# OBKP_Effector_PCB_MIKE_DID_IT.net
KiCad netlist of a schematic drawn in EAGLE
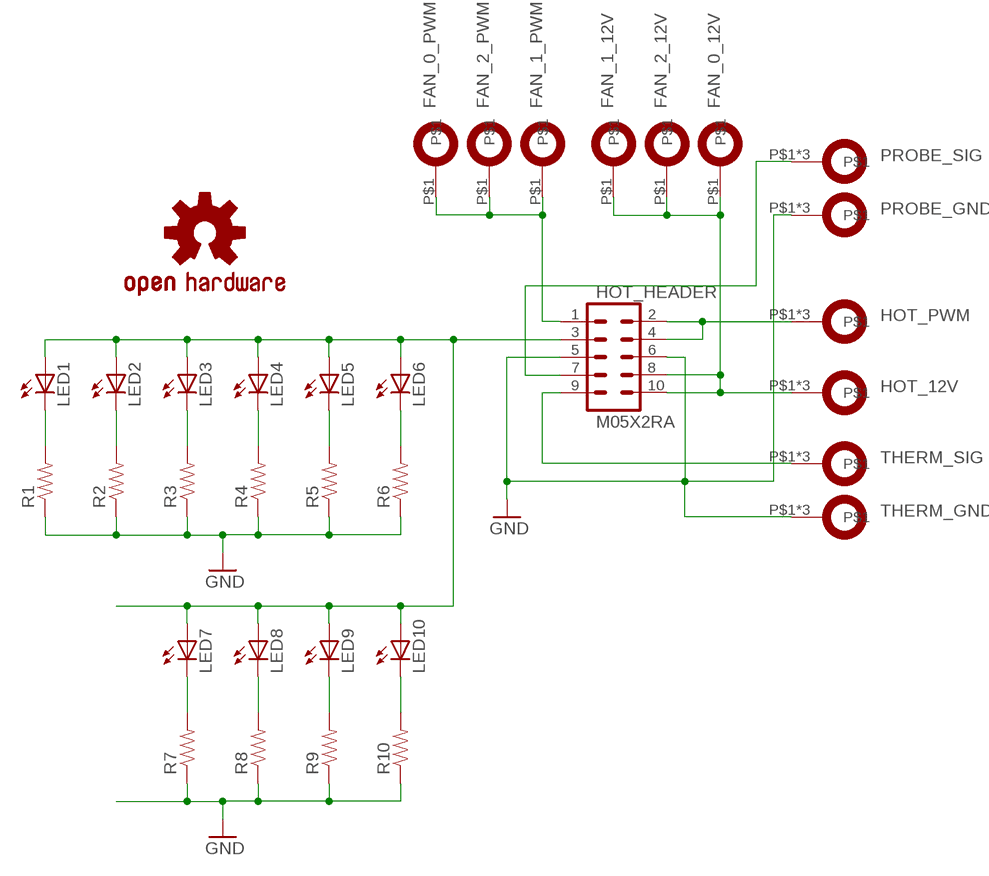
[diagram p0: schematic, sheet 1]

(export (version "E")
  (design (tool "Eeschema 10.0.6"))
  (components
    (comp (ref "FAN_0_12V")
      (value "LUG2.3")
      (footprint "eagle-import:2.3MM")
      (libsource (lib "eagle-import") (part "LUG2.3"))
    )
    (comp (ref "FAN_0_PWM")
      (value "LUG2.3")
      (footprint "eagle-import:2.3MM")
      (libsource (lib "eagle-import") (part "LUG2.3"))
    )
    (comp (ref "FAN_1_12V")
      (value "LUG2.3")
      (footprint "eagle-import:2.3MM")
      (libsource (lib "eagle-import") (part "LUG2.3"))
    )
    (comp (ref "FAN_1_PWM")
      (value "LUG2.3")
      (footprint "eagle-import:2.3MM")
      (libsource (lib "eagle-import") (part "LUG2.3"))
    )
    (comp (ref "FAN_2_12V")
      (value "LUG2.3")
      (footprint "eagle-import:2.3MM")
      (libsource (lib "eagle-import") (part "LUG2.3"))
    )
    (comp (ref "FAN_2_PWM")
      (value "LUG2.3")
      (footprint "eagle-import:2.3MM")
      (libsource (lib "eagle-import") (part "LUG2.3"))
    )
    (comp (ref "HOT_12V")
      (value "LUG3-X")
      (footprint "eagle-import:3MM")
      (libsource (lib "eagle-import") (part "LUG3-X"))
    )
    (comp (ref "HOT_HEADER")
      (value "M05X2RA")
      (footprint "eagle-import:2X5-RA")
      (libsource (lib "eagle-import") (part "M05X2RA"))
    )
    (comp (ref "HOT_PWM")
      (value "LUG3-X")
      (footprint "eagle-import:3MM")
      (libsource (lib "eagle-import") (part "LUG3-X"))
    )
    (comp (ref "LED1")
      (value "LED0805")
      (footprint "eagle-import:CHIPLED_0805")
      (libsource (lib "eagle-import") (part "LED0805"))
    )
    (comp (ref "LED2")
      (value "LED0805")
      (footprint "eagle-import:CHIPLED_0805")
      (libsource (lib "eagle-import") (part "LED0805"))
    )
    (comp (ref "LED3")
      (value "LED0805")
      (footprint "eagle-import:CHIPLED_0805")
      (libsource (lib "eagle-import") (part "LED0805"))
    )
    (comp (ref "LED4")
      (value "LED0805")
      (footprint "eagle-import:CHIPLED_0805")
      (libsource (lib "eagle-import") (part "LED0805"))
    )
    (comp (ref "LED5")
      (value "LED0805")
      (footprint "eagle-import:CHIPLED_0805")
      (libsource (lib "eagle-import") (part "LED0805"))
    )
    (comp (ref "LED6")
      (value "LED0805")
      (footprint "eagle-import:CHIPLED_0805")
      (libsource (lib "eagle-import") (part "LED0805"))
    )
    (comp (ref "LED7")
      (value "LED0805")
      (footprint "eagle-import:CHIPLED_0805")
      (libsource (lib "eagle-import") (part "LED0805"))
    )
    (comp (ref "LED8")
      (value "LED0805")
      (footprint "eagle-import:CHIPLED_0805")
      (libsource (lib "eagle-import") (part "LED0805"))
    )
    (comp (ref "LED9")
      (value "LED0805")
      (footprint "eagle-import:CHIPLED_0805")
      (libsource (lib "eagle-import") (part "LED0805"))
    )
    (comp (ref "LED10")
      (value "LED0805")
      (footprint "eagle-import:CHIPLED_0805")
      (libsource (lib "eagle-import") (part "LED0805"))
    )
    (comp (ref "LOGO1")
      (value "OSHW-LOGOS")
      (footprint "eagle-import:OSHW-LOGO-S")
      (libsource (lib "eagle-import") (part "OSHW-LOGOS"))
    )
    (comp (ref "PROBE_GND")
      (value "LUG3-X")
      (footprint "eagle-import:3MM")
      (libsource (lib "eagle-import") (part "LUG3-X"))
    )
    (comp (ref "PROBE_SIG")
      (value "LUG3-X")
      (footprint "eagle-import:3MM")
      (libsource (lib "eagle-import") (part "LUG3-X"))
    )
    (comp (ref "R1")
      (value "RESISTOR0805-RES")
      (footprint "eagle-import:0805")
      (libsource (lib "eagle-import") (part "RESISTOR0805-RES"))
    )
    (comp (ref "R2")
      (value "RESISTOR0805-RES")
      (footprint "eagle-import:0805")
      (libsource (lib "eagle-import") (part "RESISTOR0805-RES"))
    )
    (comp (ref "R3")
      (value "RESISTOR0805-RES")
      (footprint "eagle-import:0805")
      (libsource (lib "eagle-import") (part "RESISTOR0805-RES"))
    )
    (comp (ref "R4")
      (value "RESISTOR0805-RES")
      (footprint "eagle-import:0805")
      (libsource (lib "eagle-import") (part "RESISTOR0805-RES"))
    )
    (comp (ref "R5")
      (value "RESISTOR0805-RES")
      (footprint "eagle-import:0805")
      (libsource (lib "eagle-import") (part "RESISTOR0805-RES"))
    )
    (comp (ref "R6")
      (value "RESISTOR0805-RES")
      (footprint "eagle-import:0805")
      (libsource (lib "eagle-import") (part "RESISTOR0805-RES"))
    )
    (comp (ref "R7")
      (value "RESISTOR0805-RES")
      (footprint "eagle-import:0805")
      (libsource (lib "eagle-import") (part "RESISTOR0805-RES"))
    )
    (comp (ref "R8")
      (value "RESISTOR0805-RES")
      (footprint "eagle-import:0805")
      (libsource (lib "eagle-import") (part "RESISTOR0805-RES"))
    )
    (comp (ref "R9")
      (value "RESISTOR0805-RES")
      (footprint "eagle-import:0805")
      (libsource (lib "eagle-import") (part "RESISTOR0805-RES"))
    )
    (comp (ref "R10")
      (value "RESISTOR0805-RES")
      (footprint "eagle-import:0805")
      (libsource (lib "eagle-import") (part "RESISTOR0805-RES"))
    )
    (comp (ref "THERM_GND")
      (value "LUG3-X")
      (footprint "eagle-import:3MM")
      (libsource (lib "eagle-import") (part "LUG3-X"))
    )
    (comp (ref "THERM_SIG")
      (value "LUG3-X")
      (footprint "eagle-import:3MM")
      (libsource (lib "eagle-import") (part "LUG3-X"))
    )
  )
  (nets
    (net (code "1") (name "GND") (class "Default")
      (node (ref "HOT_HEADER") (pin "5") (pinfunction "5_5") (pintype "passive"))
      (node (ref "HOT_HEADER") (pin "6") (pinfunction "6_6") (pintype "passive"))
      (node (ref "PROBE_GND") (pin "P$1") (pinfunction "P$1_P$1") (pintype "bidirectional"))
      (node (ref "PROBE_GND") (pin "P$2") (pinfunction "P$1_P$2") (pintype "bidirectional"))
      (node (ref "PROBE_GND") (pin "P$3") (pinfunction "P$1_P$3") (pintype "bidirectional"))
      (node (ref "R1") (pin "1") (pinfunction "1_1") (pintype "passive"))
      (node (ref "R10") (pin "1") (pinfunction "1_1") (pintype "passive"))
      (node (ref "R2") (pin "1") (pinfunction "1_1") (pintype "passive"))
      (node (ref "R3") (pin "1") (pinfunction "1_1") (pintype "passive"))
      (node (ref "R4") (pin "1") (pinfunction "1_1") (pintype "passive"))
      (node (ref "R5") (pin "1") (pinfunction "1_1") (pintype "passive"))
      (node (ref "R6") (pin "1") (pinfunction "1_1") (pintype "passive"))
      (node (ref "R7") (pin "1") (pinfunction "1_1") (pintype "passive"))
      (node (ref "R8") (pin "1") (pinfunction "1_1") (pintype "passive"))
      (node (ref "R9") (pin "1") (pinfunction "1_1") (pintype "passive"))
      (node (ref "THERM_GND") (pin "P$1") (pinfunction "P$1_P$1") (pintype "bidirectional"))
      (node (ref "THERM_GND") (pin "P$2") (pinfunction "P$1_P$2") (pintype "bidirectional"))
      (node (ref "THERM_GND") (pin "P$3") (pinfunction "P$1_P$3") (pintype "bidirectional"))
    )
    (net (code "2") (name "Net-(FAN_0_12V-PadP$1)") (class "Default")
      (node (ref "FAN_0_12V") (pin "P$1") (pinfunction "P$1_P$1") (pintype "bidirectional"))
      (node (ref "FAN_1_12V") (pin "P$1") (pinfunction "P$1_P$1") (pintype "bidirectional"))
      (node (ref "FAN_2_12V") (pin "P$1") (pinfunction "P$1_P$1") (pintype "bidirectional"))
      (node (ref "HOT_12V") (pin "P$1") (pinfunction "P$1_P$1") (pintype "bidirectional"))
      (node (ref "HOT_12V") (pin "P$2") (pinfunction "P$1_P$2") (pintype "bidirectional"))
      (node (ref "HOT_12V") (pin "P$3") (pinfunction "P$1_P$3") (pintype "bidirectional"))
      (node (ref "HOT_HEADER") (pin "10") (pinfunction "10_10") (pintype "passive"))
      (node (ref "HOT_HEADER") (pin "8") (pinfunction "8_8") (pintype "passive"))
    )
    (net (code "3") (name "Net-(FAN_0_PWM-PadP$1)") (class "Default")
      (node (ref "FAN_0_PWM") (pin "P$1") (pinfunction "P$1_P$1") (pintype "bidirectional"))
      (node (ref "FAN_1_PWM") (pin "P$1") (pinfunction "P$1_P$1") (pintype "bidirectional"))
      (node (ref "FAN_2_PWM") (pin "P$1") (pinfunction "P$1_P$1") (pintype "bidirectional"))
      (node (ref "HOT_HEADER") (pin "1") (pinfunction "1_1") (pintype "passive"))
    )
    (net (code "4") (name "Net-(HOT_HEADER-Pad2)") (class "Default")
      (node (ref "HOT_HEADER") (pin "2") (pinfunction "2_2") (pintype "passive"))
      (node (ref "HOT_HEADER") (pin "4") (pinfunction "4_4") (pintype "passive"))
      (node (ref "HOT_PWM") (pin "P$1") (pinfunction "P$1_P$1") (pintype "bidirectional"))
      (node (ref "HOT_PWM") (pin "P$2") (pinfunction "P$1_P$2") (pintype "bidirectional"))
      (node (ref "HOT_PWM") (pin "P$3") (pinfunction "P$1_P$3") (pintype "bidirectional"))
    )
    (net (code "5") (name "Net-(HOT_HEADER-Pad3)") (class "Default")
      (node (ref "HOT_HEADER") (pin "3") (pinfunction "3_3") (pintype "passive"))
      (node (ref "LED1") (pin "A") (pinfunction "A_A") (pintype "passive"))
      (node (ref "LED10") (pin "A") (pinfunction "A_A") (pintype "passive"))
      (node (ref "LED2") (pin "A") (pinfunction "A_A") (pintype "passive"))
      (node (ref "LED3") (pin "A") (pinfunction "A_A") (pintype "passive"))
      (node (ref "LED4") (pin "A") (pinfunction "A_A") (pintype "passive"))
      (node (ref "LED5") (pin "A") (pinfunction "A_A") (pintype "passive"))
      (node (ref "LED6") (pin "A") (pinfunction "A_A") (pintype "passive"))
      (node (ref "LED7") (pin "A") (pinfunction "A_A") (pintype "passive"))
      (node (ref "LED8") (pin "A") (pinfunction "A_A") (pintype "passive"))
      (node (ref "LED9") (pin "A") (pinfunction "A_A") (pintype "passive"))
    )
    (net (code "6") (name "Net-(HOT_HEADER-Pad7)") (class "Default")
      (node (ref "HOT_HEADER") (pin "7") (pinfunction "7_7") (pintype "passive"))
      (node (ref "PROBE_SIG") (pin "P$1") (pinfunction "P$1_P$1") (pintype "bidirectional"))
      (node (ref "PROBE_SIG") (pin "P$2") (pinfunction "P$1_P$2") (pintype "bidirectional"))
      (node (ref "PROBE_SIG") (pin "P$3") (pinfunction "P$1_P$3") (pintype "bidirectional"))
    )
    (net (code "7") (name "Net-(HOT_HEADER-Pad9)") (class "Default")
      (node (ref "HOT_HEADER") (pin "9") (pinfunction "9_9") (pintype "passive"))
      (node (ref "THERM_SIG") (pin "P$1") (pinfunction "P$1_P$1") (pintype "bidirectional"))
      (node (ref "THERM_SIG") (pin "P$2") (pinfunction "P$1_P$2") (pintype "bidirectional"))
      (node (ref "THERM_SIG") (pin "P$3") (pinfunction "P$1_P$3") (pintype "bidirectional"))
    )
    (net (code "8") (name "Net-(LED1-PadC)") (class "Default")
      (node (ref "LED1") (pin "C") (pinfunction "C_C") (pintype "passive"))
      (node (ref "R1") (pin "2") (pinfunction "2_2") (pintype "passive"))
    )
    (net (code "9") (name "Net-(LED2-PadC)") (class "Default")
      (node (ref "LED2") (pin "C") (pinfunction "C_C") (pintype "passive"))
      (node (ref "R2") (pin "2") (pinfunction "2_2") (pintype "passive"))
    )
    (net (code "10") (name "Net-(LED3-PadC)") (class "Default")
      (node (ref "LED3") (pin "C") (pinfunction "C_C") (pintype "passive"))
      (node (ref "R3") (pin "2") (pinfunction "2_2") (pintype "passive"))
    )
    (net (code "11") (name "Net-(LED4-PadC)") (class "Default")
      (node (ref "LED4") (pin "C") (pinfunction "C_C") (pintype "passive"))
      (node (ref "R4") (pin "2") (pinfunction "2_2") (pintype "passive"))
    )
    (net (code "12") (name "Net-(LED5-PadC)") (class "Default")
      (node (ref "LED5") (pin "C") (pinfunction "C_C") (pintype "passive"))
      (node (ref "R5") (pin "2") (pinfunction "2_2") (pintype "passive"))
    )
    (net (code "13") (name "Net-(LED6-PadC)") (class "Default")
      (node (ref "LED6") (pin "C") (pinfunction "C_C") (pintype "passive"))
      (node (ref "R6") (pin "2") (pinfunction "2_2") (pintype "passive"))
    )
    (net (code "14") (name "Net-(LED7-PadC)") (class "Default")
      (node (ref "LED7") (pin "C") (pinfunction "C_C") (pintype "passive"))
      (node (ref "R7") (pin "2") (pinfunction "2_2") (pintype "passive"))
    )
    (net (code "15") (name "Net-(LED8-PadC)") (class "Default")
      (node (ref "LED8") (pin "C") (pinfunction "C_C") (pintype "passive"))
      (node (ref "R8") (pin "2") (pinfunction "2_2") (pintype "passive"))
    )
    (net (code "16") (name "Net-(LED9-PadC)") (class "Default")
      (node (ref "LED9") (pin "C") (pinfunction "C_C") (pintype "passive"))
      (node (ref "R9") (pin "2") (pinfunction "2_2") (pintype "passive"))
    )
    (net (code "17") (name "Net-(LED10-PadC)") (class "Default")
      (node (ref "LED10") (pin "C") (pinfunction "C_C") (pintype "passive"))
      (node (ref "R10") (pin "2") (pinfunction "2_2") (pintype "passive"))
    )
  )
)
